# SnifferRS232.net
KiCad netlist of a schematic drawn in Altium Designer
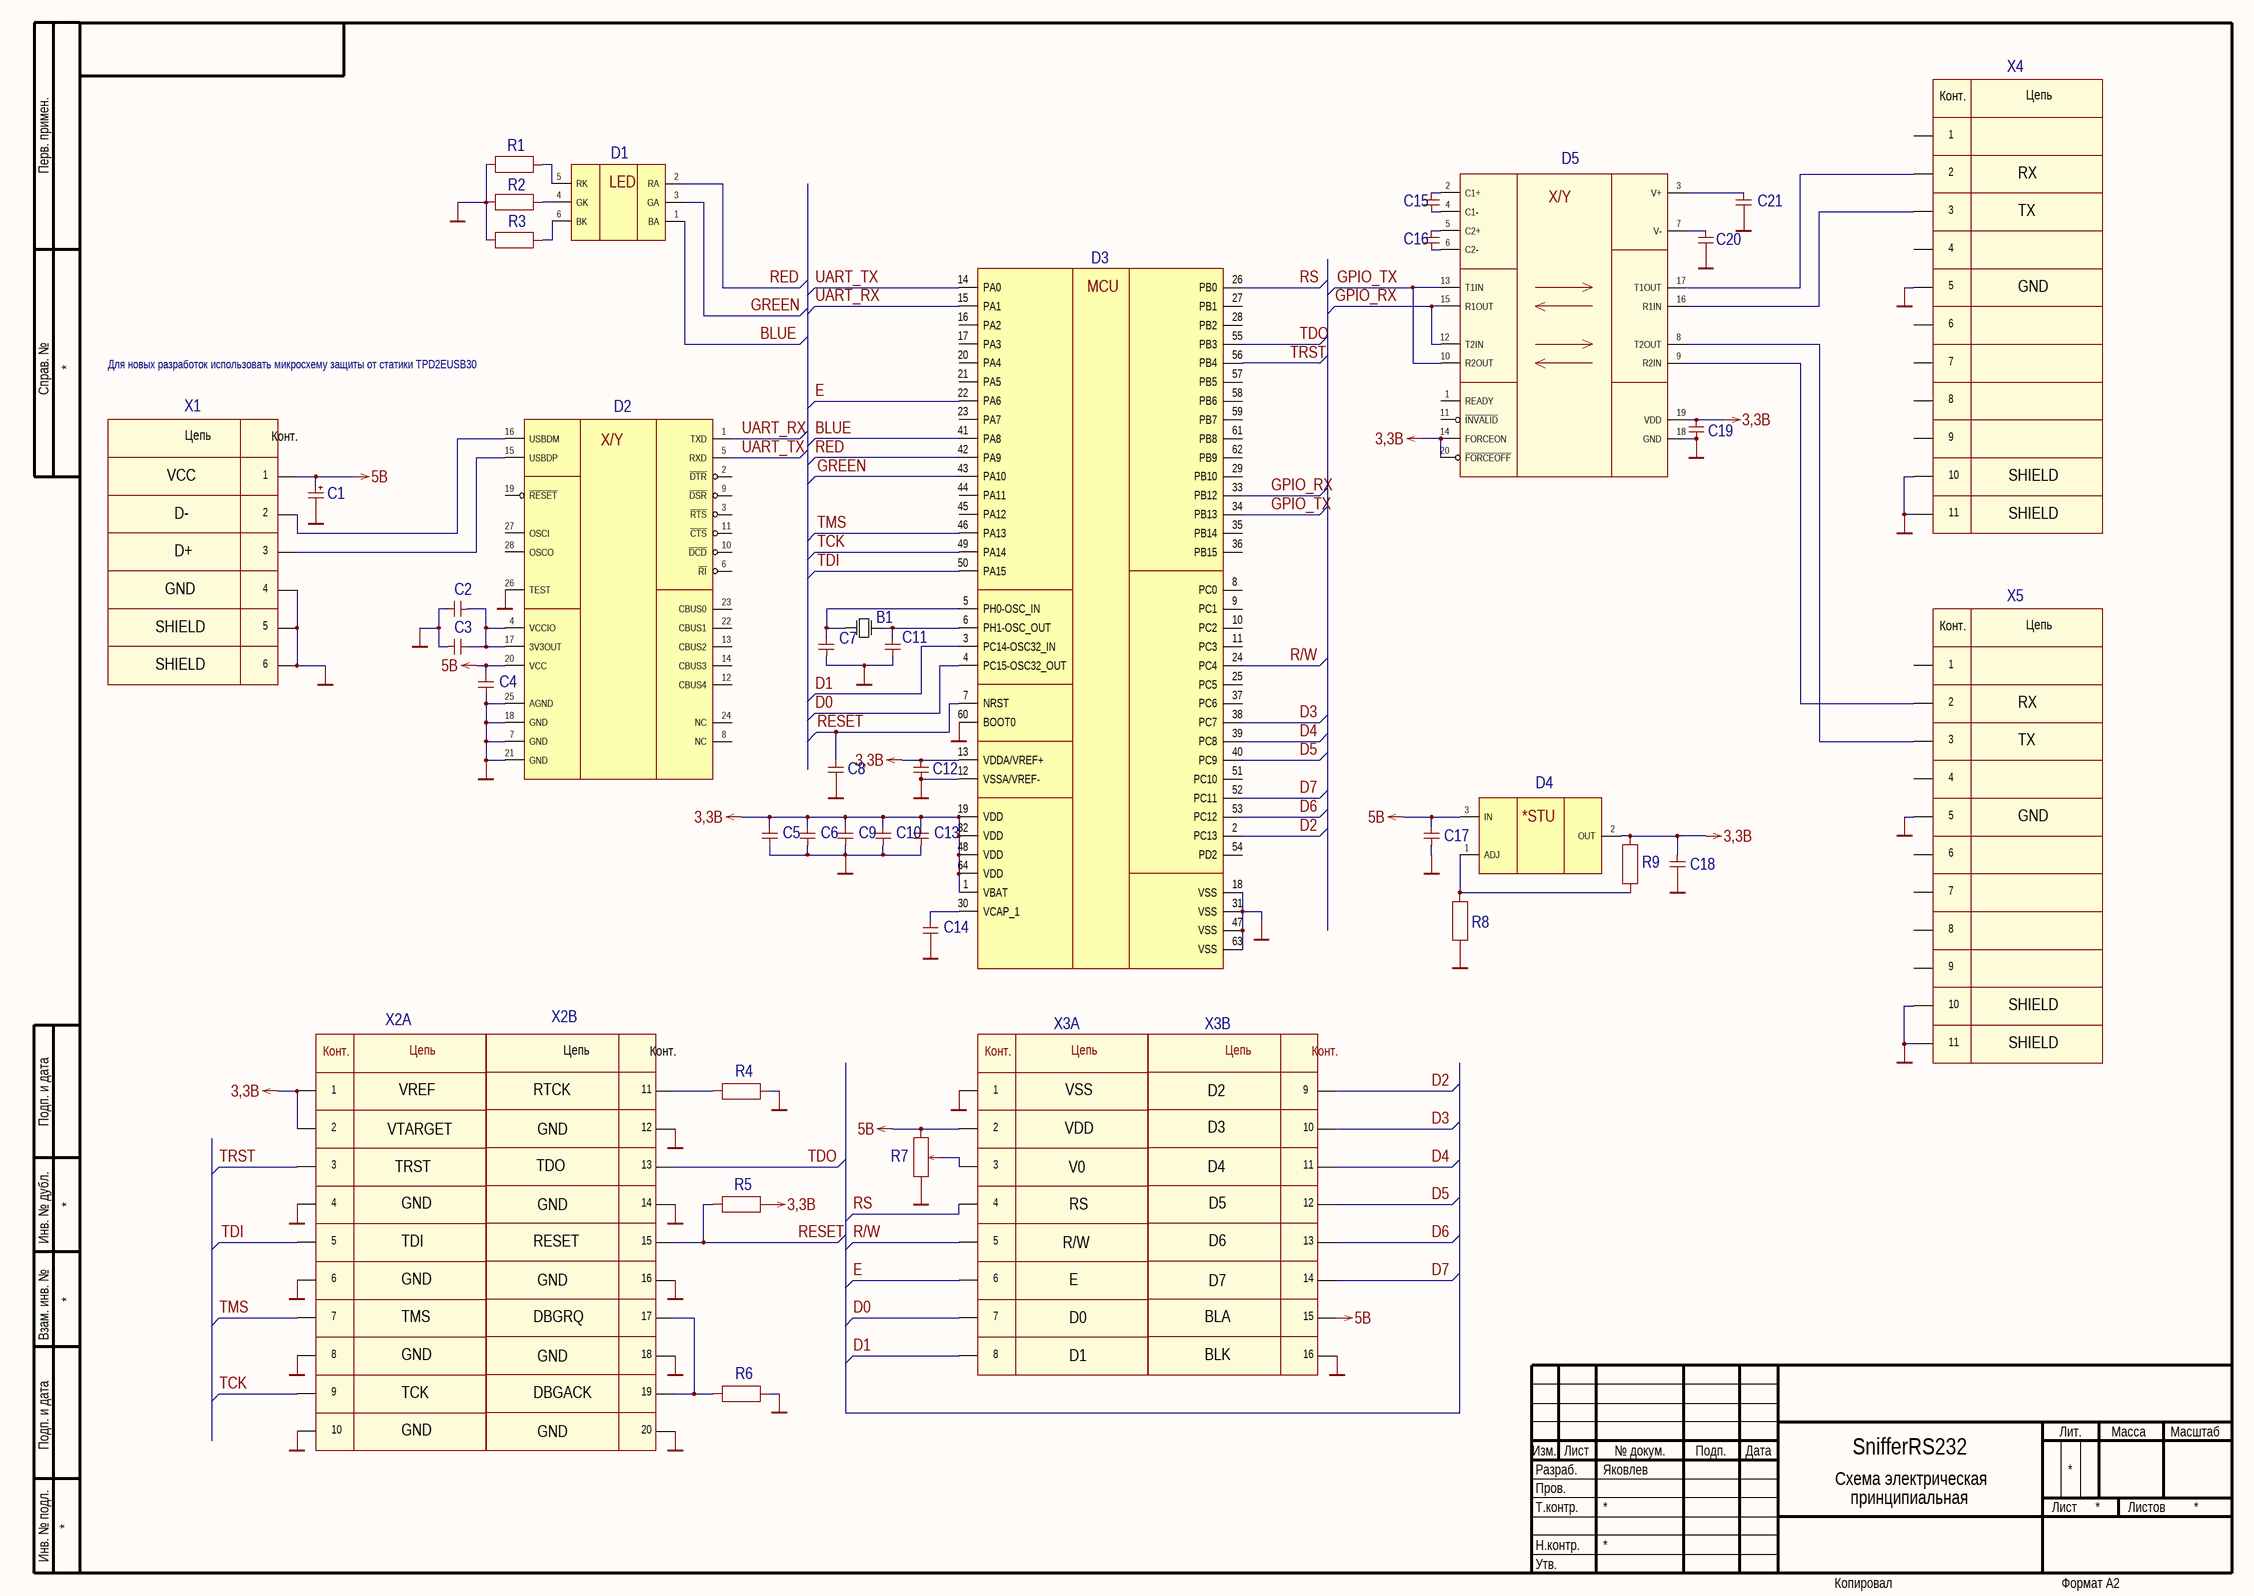
[diagram p0: SnifferRS232.SchDoc]

(export (version "E")
  (design (tool "Eeschema 10.0.6"))
  (components
    (comp (ref "B1")
      (value "ZQ1 KX-3H 25.0 MHz")
      (footprint "KX-3H")
      (description "Crystal oscillator")
      (fields (field (name "MANUFACTURER") "Geyer Electronic"))
      (libsource (lib "Devices") (part "Oscillator"))
    )
    (comp (ref "C1")
      (value "1208-16 В-100мкФ")
      (footprint "CAP_5x11")
      (description "Electrolytic capacitor")
      (libsource (lib "Passive,Diodes") (part "Cap_el"))
    )
    (comp (ref "C2")
      (value "0805-16 В-X7R-0,1мкФ±10 %")
      (footprint "SMD-0805C")
      (description "Capacitor")
      (libsource (lib "Passive,Diodes") (part "Cap"))
    )
    (comp (ref "C3")
      (value "0805-16 В-X7R-0,1мкФ±10 %")
      (footprint "SMD-0805C")
      (description "Capacitor")
      (libsource (lib "Passive,Diodes") (part "Cap"))
    )
    (comp (ref "C4")
      (value "0805-16 В-X7R-0,1мкФ±10 %")
      (footprint "SMD-0805C")
      (description "Capacitor")
      (libsource (lib "Passive,Diodes") (part "Cap"))
    )
    (comp (ref "C5")
      (value "0805-16 В-X7R-0,1мкФ±10 %")
      (footprint "SMD-0805C")
      (description "Capacitor")
      (libsource (lib "Passive,Diodes") (part "Cap"))
    )
    (comp (ref "C6")
      (value "0805-16 В-X7R-0,1мкФ±10 %")
      (footprint "SMD-0805C")
      (description "Capacitor")
      (libsource (lib "Passive,Diodes") (part "Cap"))
    )
    (comp (ref "C7")
      (value "0805-50 В-COG-22пФ±5 %")
      (footprint "SMD-0805C")
      (description "Capacitor")
      (libsource (lib "Passive,Diodes") (part "Cap"))
    )
    (comp (ref "C8")
      (value "0805-16 В-X7R-0,1мкФ±10 %")
      (footprint "SMD-0805C")
      (description "Capacitor")
      (libsource (lib "Passive,Diodes") (part "Cap"))
    )
    (comp (ref "C9")
      (value "0805-16 В-X7R-0,1мкФ±10 %")
      (footprint "SMD-0805C")
      (description "Capacitor")
      (libsource (lib "Passive,Diodes") (part "Cap"))
    )
    (comp (ref "C10")
      (value "0805-16 В-X7R-0,1мкФ±10 %")
      (footprint "SMD-0805C")
      (description "Capacitor")
      (libsource (lib "Passive,Diodes") (part "Cap"))
    )
    (comp (ref "C11")
      (value "0805-50 В-COG-22пФ±5 %")
      (footprint "SMD-0805C")
      (description "Capacitor")
      (libsource (lib "Passive,Diodes") (part "Cap"))
    )
    (comp (ref "C12")
      (value "0805-16 В-X7R-0,1мкФ±10 %")
      (footprint "SMD-0805C")
      (description "Capacitor")
      (libsource (lib "Passive,Diodes") (part "Cap"))
    )
    (comp (ref "C13")
      (value "0805-16 В-X7R-0,1мкФ±10 %")
      (footprint "SMD-0805C")
      (description "Capacitor")
      (libsource (lib "Passive,Diodes") (part "Cap"))
    )
    (comp (ref "C14")
      (value "0805-16 В-X7R-4,7мкФ±10 %")
      (footprint "SMD-0805C")
      (description "Capacitor")
      (libsource (lib "Passive,Diodes") (part "Cap"))
    )
    (comp (ref "C15")
      (value "0805-16 В-X7R-0,1мкФ±10 %")
      (footprint "SMD-0805C")
      (description "Capacitor")
      (libsource (lib "Passive,Diodes") (part "Cap"))
    )
    (comp (ref "C16")
      (value "0805-16 В-X7R-0,1мкФ±10 %")
      (footprint "SMD-0805C")
      (description "Capacitor")
      (libsource (lib "Passive,Diodes") (part "Cap"))
    )
    (comp (ref "C17")
      (value "0805-16 В-X7R-1мкФ±10 %")
      (footprint "SMD-0805C")
      (description "Capacitor")
      (libsource (lib "Passive,Diodes") (part "Cap"))
    )
    (comp (ref "C18")
      (value "0805-16 В-X7R-1мкФ±10 %")
      (footprint "SMD-0805C")
      (description "Capacitor")
      (libsource (lib "Passive,Diodes") (part "Cap"))
    )
    (comp (ref "C19")
      (value "0805-16 В-X7R-0,1мкФ±10 %")
      (footprint "SMD-0805C")
      (description "Capacitor")
      (libsource (lib "Passive,Diodes") (part "Cap"))
    )
    (comp (ref "C20")
      (value "0805-16 В-X7R-0,1мкФ±10 %")
      (footprint "SMD-0805C")
      (description "Capacitor")
      (libsource (lib "Passive,Diodes") (part "Cap"))
    )
    (comp (ref "C21")
      (value "0805-16 В-X7R-0,1мкФ±10 %")
      (footprint "SMD-0805C")
      (description "Capacitor")
      (libsource (lib "Passive,Diodes") (part "Cap"))
    )
    (comp (ref "D1")
      (value "TO-5050BC-MRPBFGF")
      (footprint "smd_50x50")
      (description "Surface mount smd LED")
      (fields (field (name "MANUFACTURER") "Oasis Technology"))
      (libsource (lib "Devices") (part "LED_RGB"))
    )
    (comp (ref "D2")
      (value "FT232RL")
      (footprint "SSOP-28_M")
      (description "USB UART Asynchronous Serial Data Transfer Chip, SSOP-28, Tape and Reel")
      (fields (field (name "MANUFACTURER") "FTDI"))
      (libsource (lib "Devices") (part "FT232R"))
    )
    (comp (ref "D3")
      (value "STM32F446RCT6")
      (footprint "LQFP64")
      (fields (field (name "MANUFACTURER") "STMicroelectronics"))
      (libsource (lib "Devices") (part "STM32F446RxT"))
    )
    (comp (ref "D4")
      (value "LM317DCYR")
      (footprint "Devices:SOT223_M")
      (description "3-Terminal Adjustable Regulator")
      (fields (field (name "MANUFACTURER") "Texas Instruments"))
      (libsource (lib "Devices") (part "LM317"))
    )
    (comp (ref "D5")
      (value "MAX3225ECAP+")
      (footprint "TSSOP-20")
      (description "±15kV ESD-Protected, 1µA, 1Mbps, 3.0V to 5.5V,  RS-232 Transceivers with AutoShutdown Plus")
      (fields (field (name "MANUFACTURER") "Maxim Integrated"))
      (libsource (lib "Devices") (part "MAX3225"))
    )
    (comp (ref "R1")
      (value "0805±5 %-680 Ом")
      (footprint "SMD-0805-RES")
      (description "Resistor")
      (libsource (lib "") (part "Res_1"))
    )
    (comp (ref "R2")
      (value "0805±5 %-680 Ом")
      (footprint "SMD-0805-RES")
      (description "Resistor")
      (libsource (lib "") (part "Res_1"))
    )
    (comp (ref "R3")
      (value "0805±5 %-0 Ом")
      (footprint "SMD-0805-RES")
      (description "Resistor")
      (libsource (lib "") (part "Res_1"))
    )
    (comp (ref "R4")
      (value "0805±5 %-10 кОм")
      (footprint "SMD-0805-RES")
      (description "Resistor")
      (libsource (lib "Passive,Diodes") (part "Res"))
    )
    (comp (ref "R5")
      (value "0805±5 %-10 кОм")
      (footprint "SMD-0805-RES")
      (description "Resistor")
      (libsource (lib "") (part "Res_1"))
    )
    (comp (ref "R6")
      (value "0805±5 %-10 кОм")
      (footprint "SMD-0805-RES")
      (description "Resistor")
      (libsource (lib "Passive,Diodes") (part "Res"))
    )
    (comp (ref "R7")
      (value "CA9PV10-10KA2020")
      (footprint "CA9V")
      (description "Potentiometer")
      (fields (field (name "MANUFACTURER") "ACP Technologies"))
      (libsource (lib "Passive,Diodes") (part "Potentiometer"))
    )
    (comp (ref "R8")
      (value "0805±1 %-2 кОм")
      (footprint "SMD-0805-RES")
      (description "Resistor")
      (libsource (lib "") (part "Res_1"))
    )
    (comp (ref "R9")
      (value "0805±1 %-1,3 кОм")
      (footprint "SMD-0805-RES")
      (description "Resistor")
      (libsource (lib "Passive,Diodes") (part "Res"))
    )
    (comp (ref "X1")
      (value "DS1099-BN0")
      (footprint "FCI USB 61729-0010BLF")
      (description "USB-B connector")
      (fields (field (name "MANUFACTURER") "Connfly Electronic"))
      (libsource (lib "Connectors") (part "USB-B"))
    )
    (comp (ref "X2")
      (value "DS1021-2*10SF11-B")
      (footprint "PLD2x10")
      (description "PLD-20 connector")
      (fields (field (name "MANUFACTURER") "Connfly Electronic"))
      (libsource (lib "") (part "PLD2x10_1"))
    )
    (comp (ref "X3")
      (value "DS1021-1*16SF112")
      (footprint "PLS-16_12")
      (description "PLD-16 connector")
      (fields (field (name "MANUFACTURER") "Connfly  Electronic"))
      (libsource (lib "") (part "PLD2x8_1"))
    )
    (comp (ref "X4")
      (value "DS1037-09FNAKT74-0CC")
      (footprint "DB-9F")
      (description "DB-9 female connector")
      (fields (field (name "MANUFACTURER") "Connfly Electronic"))
      (libsource (lib "Connectors") (part "DB-9"))
    )
    (comp (ref "X5")
      (value "DS1037-09MNAKT74-0CC")
      (footprint "DB-9M")
      (description "DB-9 male connector")
      (fields (field (name "MANUFACTURER") "Connfly Electronic"))
      (libsource (lib "Connectors") (part "DB-9"))
    )
  )
  (nets
    (net (code "1") (name "/BLUE") (class "Default")
      (node (ref "D1") (pin "1") (pinfunction "BA_1") (pintype "passive"))
      (node (ref "D3") (pin "41") (pinfunction "PA8_41") (pintype "passive"))
    )
    (net (code "2") (name "/D0") (class "Default")
      (node (ref "D3") (pin "4") (pinfunction "PC15-OSC32_OUT_4") (pintype "passive"))
      (node (ref "X3") (pin "7") (pinfunction "7_7") (pintype "passive"))
    )
    (net (code "3") (name "/D1") (class "Default")
      (node (ref "D3") (pin "3") (pinfunction "PC14-OSC32_IN_3") (pintype "passive"))
      (node (ref "X3") (pin "8") (pinfunction "8_8") (pintype "passive"))
    )
    (net (code "4") (name "/D2") (class "Default")
      (node (ref "D3") (pin "2") (pinfunction "PC13_2") (pintype "passive"))
      (node (ref "X3") (pin "9") (pinfunction "9_9") (pintype "passive"))
    )
    (net (code "5") (name "/D3") (class "Default")
      (node (ref "D3") (pin "38") (pinfunction "PC7_38") (pintype "passive"))
      (node (ref "X3") (pin "10") (pinfunction "10_10") (pintype "passive"))
    )
    (net (code "6") (name "/D4") (class "Default")
      (node (ref "D3") (pin "39") (pinfunction "PC8_39") (pintype "passive"))
      (node (ref "X3") (pin "11") (pinfunction "11_11") (pintype "passive"))
    )
    (net (code "7") (name "/D5") (class "Default")
      (node (ref "D3") (pin "40") (pinfunction "PC9_40") (pintype "passive"))
      (node (ref "X3") (pin "12") (pinfunction "12_12") (pintype "passive"))
    )
    (net (code "8") (name "/D6") (class "Default")
      (node (ref "D3") (pin "53") (pinfunction "PC12_53") (pintype "passive"))
      (node (ref "X3") (pin "13") (pinfunction "13_13") (pintype "passive"))
    )
    (net (code "9") (name "/D7") (class "Default")
      (node (ref "D3") (pin "52") (pinfunction "PC11_52") (pintype "passive"))
      (node (ref "X3") (pin "14") (pinfunction "14_14") (pintype "passive"))
    )
    (net (code "10") (name "/E") (class "Default")
      (node (ref "D3") (pin "22") (pinfunction "PA6_22") (pintype "passive"))
      (node (ref "X3") (pin "6") (pinfunction "6_6") (pintype "passive"))
    )
    (net (code "11") (name "/GPIO_RX") (class "Default")
      (node (ref "D3") (pin "33") (pinfunction "PB12_33") (pintype "passive"))
      (node (ref "D5") (pin "12") (pinfunction "T2IN_12") (pintype "passive"))
      (node (ref "D5") (pin "15") (pinfunction "R1OUT_15") (pintype "passive"))
    )
    (net (code "12") (name "/GPIO_TX") (class "Default")
      (node (ref "D3") (pin "34") (pinfunction "PB13_34") (pintype "passive"))
      (node (ref "D5") (pin "10") (pinfunction "R2OUT_10") (pintype "passive"))
      (node (ref "D5") (pin "13") (pinfunction "T1IN_13") (pintype "passive"))
    )
    (net (code "13") (name "/GREEN") (class "Default")
      (node (ref "D1") (pin "3") (pinfunction "GA_3") (pintype "passive"))
      (node (ref "D3") (pin "43") (pinfunction "PA10_43") (pintype "passive"))
    )
    (net (code "14") (name "/RED") (class "Default")
      (node (ref "D1") (pin "2") (pinfunction "RA_2") (pintype "passive"))
      (node (ref "D3") (pin "42") (pinfunction "PA9_42") (pintype "passive"))
    )
    (net (code "15") (name "/RESET") (class "Default")
      (node (ref "C8") (pin "1") (pinfunction "1_1") (pintype "passive"))
      (node (ref "D3") (pin "7") (pinfunction "NRST_7") (pintype "passive"))
      (node (ref "R5") (pin "2") (pinfunction "2_2") (pintype "passive"))
      (node (ref "X2") (pin "15") (pinfunction "15_15") (pintype "passive"))
    )
    (net (code "16") (name "/RS") (class "Default")
      (node (ref "D3") (pin "26") (pinfunction "PB0_26") (pintype "passive"))
      (node (ref "X3") (pin "4") (pinfunction "4_4") (pintype "passive"))
    )
    (net (code "17") (name "/R{slash}W") (class "Default")
      (node (ref "D3") (pin "24") (pinfunction "PC4_24") (pintype "passive"))
      (node (ref "X3") (pin "5") (pinfunction "5_5") (pintype "passive"))
    )
    (net (code "18") (name "/TCK") (class "Default")
      (node (ref "D3") (pin "49") (pinfunction "PA14_49") (pintype "passive"))
      (node (ref "X2") (pin "9") (pinfunction "9_9") (pintype "passive"))
    )
    (net (code "19") (name "/TDI") (class "Default")
      (node (ref "D3") (pin "50") (pinfunction "PA15_50") (pintype "passive"))
      (node (ref "X2") (pin "5") (pinfunction "5_5") (pintype "passive"))
    )
    (net (code "20") (name "/TDO") (class "Default")
      (node (ref "D3") (pin "55") (pinfunction "PB3_55") (pintype "passive"))
      (node (ref "X2") (pin "13") (pinfunction "13_13") (pintype "passive"))
    )
    (net (code "21") (name "/TMS") (class "Default")
      (node (ref "D3") (pin "46") (pinfunction "PA13_46") (pintype "passive"))
      (node (ref "X2") (pin "7") (pinfunction "7_7") (pintype "passive"))
    )
    (net (code "22") (name "/TRST") (class "Default")
      (node (ref "D3") (pin "56") (pinfunction "PB4_56") (pintype "passive"))
      (node (ref "X2") (pin "3") (pinfunction "3_3") (pintype "passive"))
    )
    (net (code "23") (name "/UART_RX") (class "Default")
      (node (ref "D2") (pin "1") (pinfunction "TXD_1") (pintype "passive"))
      (node (ref "D3") (pin "15") (pinfunction "PA1_15") (pintype "passive"))
    )
    (net (code "24") (name "/UART_TX") (class "Default")
      (node (ref "D2") (pin "5") (pinfunction "RXD_5") (pintype "passive"))
      (node (ref "D3") (pin "14") (pinfunction "PA0_14") (pintype "passive"))
    )
    (net (code "25") (name "3,3В") (class "Default")
      (node (ref "C10") (pin "1") (pinfunction "1_1") (pintype "passive"))
      (node (ref "C12") (pin "1") (pinfunction "1_1") (pintype "passive"))
      (node (ref "C13") (pin "1") (pinfunction "1_1") (pintype "passive"))
      (node (ref "C18") (pin "2") (pinfunction "2_2") (pintype "passive"))
      (node (ref "C19") (pin "1") (pinfunction "1_1") (pintype "passive"))
      (node (ref "C5") (pin "1") (pinfunction "1_1") (pintype "passive"))
      (node (ref "C6") (pin "1") (pinfunction "1_1") (pintype "passive"))
      (node (ref "C9") (pin "1") (pinfunction "1_1") (pintype "passive"))
      (node (ref "D3") (pin "1") (pinfunction "VBAT_1") (pintype "power_in"))
      (node (ref "D3") (pin "13") (pinfunction "VDDA/VREF+_13") (pintype "power_in"))
      (node (ref "D3") (pin "19") (pinfunction "VDD_19") (pintype "power_in"))
      (node (ref "D3") (pin "32") (pinfunction "VDD_32") (pintype "power_in"))
      (node (ref "D3") (pin "48") (pinfunction "VDD_48") (pintype "power_in"))
      (node (ref "D3") (pin "64") (pinfunction "VDD_64") (pintype "power_in"))
      (node (ref "D4") (pin "2") (pinfunction "OUT_2") (pintype "power_in"))
      (node (ref "D5") (pin "14") (pinfunction "FORCEON_14") (pintype "passive"))
      (node (ref "D5") (pin "19") (pinfunction "VDD_19") (pintype "power_in"))
      (node (ref "D5") (pin "20") (pinfunction "~{FORCEOFF}_20") (pintype "passive"))
      (node (ref "R5") (pin "1") (pinfunction "1_1") (pintype "passive"))
      (node (ref "R9") (pin "2") (pinfunction "2_2") (pintype "passive"))
      (node (ref "X2") (pin "1") (pinfunction "1_1") (pintype "passive"))
      (node (ref "X2") (pin "2") (pinfunction "2_2") (pintype "passive"))
    )
    (net (code "26") (name "5В") (class "Default")
      (node (ref "C1") (pin "1") (pinfunction "1_1") (pintype "passive"))
      (node (ref "C17") (pin "2") (pinfunction "2_2") (pintype "passive"))
      (node (ref "C4") (pin "1") (pinfunction "1_1") (pintype "passive"))
      (node (ref "D2") (pin "20") (pinfunction "VCC_20") (pintype "power_in"))
      (node (ref "D4") (pin "3") (pinfunction "IN_3") (pintype "power_in"))
      (node (ref "R7") (pin "3") (pinfunction "3_3") (pintype "passive"))
      (node (ref "X1") (pin "1") (pinfunction "1_1") (pintype "passive"))
      (node (ref "X3") (pin "15") (pinfunction "15_15") (pintype "passive"))
      (node (ref "X3") (pin "2") (pinfunction "2_2") (pintype "passive"))
    )
    (net (code "27") (name "GND") (class "Default")
      (node (ref "C1") (pin "2") (pinfunction "2_2") (pintype "passive"))
      (node (ref "C10") (pin "2") (pinfunction "2_2") (pintype "passive"))
      (node (ref "C11") (pin "2") (pinfunction "2_2") (pintype "passive"))
      (node (ref "C12") (pin "2") (pinfunction "2_2") (pintype "passive"))
      (node (ref "C13") (pin "2") (pinfunction "2_2") (pintype "passive"))
      (node (ref "C14") (pin "2") (pinfunction "2_2") (pintype "passive"))
      (node (ref "C17") (pin "1") (pinfunction "1_1") (pintype "passive"))
      (node (ref "C18") (pin "1") (pinfunction "1_1") (pintype "passive"))
      (node (ref "C19") (pin "2") (pinfunction "2_2") (pintype "passive"))
      (node (ref "C2") (pin "1") (pinfunction "1_1") (pintype "passive"))
      (node (ref "C20") (pin "2") (pinfunction "2_2") (pintype "passive"))
      (node (ref "C21") (pin "2") (pinfunction "2_2") (pintype "passive"))
      (node (ref "C3") (pin "1") (pinfunction "1_1") (pintype "passive"))
      (node (ref "C4") (pin "2") (pinfunction "2_2") (pintype "passive"))
      (node (ref "C5") (pin "2") (pinfunction "2_2") (pintype "passive"))
      (node (ref "C6") (pin "2") (pinfunction "2_2") (pintype "passive"))
      (node (ref "C7") (pin "2") (pinfunction "2_2") (pintype "passive"))
      (node (ref "C8") (pin "2") (pinfunction "2_2") (pintype "passive"))
      (node (ref "C9") (pin "2") (pinfunction "2_2") (pintype "passive"))
      (node (ref "D2") (pin "18") (pinfunction "GND_18") (pintype "power_in"))
      (node (ref "D2") (pin "21") (pinfunction "GND_21") (pintype "power_in"))
      (node (ref "D2") (pin "25") (pinfunction "AGND_25") (pintype "power_in"))
      (node (ref "D2") (pin "26") (pinfunction "TEST_26") (pintype "passive"))
      (node (ref "D2") (pin "7") (pinfunction "GND_7") (pintype "power_in"))
      (node (ref "D3") (pin "12") (pinfunction "VSSA/VREF-_12") (pintype "power_in"))
      (node (ref "D3") (pin "18") (pinfunction "VSS_18") (pintype "power_in"))
      (node (ref "D3") (pin "31") (pinfunction "VSS_31") (pintype "power_in"))
      (node (ref "D3") (pin "47") (pinfunction "VSS_47") (pintype "power_in"))
      (node (ref "D3") (pin "60") (pinfunction "BOOT0_60") (pintype "passive"))
      (node (ref "D3") (pin "63") (pinfunction "VSS_63") (pintype "power_in"))
      (node (ref "D5") (pin "18") (pinfunction "GND_18") (pintype "power_in"))
      (node (ref "R1") (pin "2") (pinfunction "2_2") (pintype "passive"))
      (node (ref "R2") (pin "2") (pinfunction "2_2") (pintype "passive"))
      (node (ref "R3") (pin "2") (pinfunction "2_2") (pintype "passive"))
      (node (ref "R4") (pin "2") (pinfunction "2_2") (pintype "passive"))
      (node (ref "R6") (pin "2") (pinfunction "2_2") (pintype "passive"))
      (node (ref "R7") (pin "1") (pinfunction "1_1") (pintype "passive"))
      (node (ref "R8") (pin "2") (pinfunction "2_2") (pintype "passive"))
      (node (ref "X1") (pin "4") (pinfunction "4_4") (pintype "passive"))
      (node (ref "X1") (pin "5") (pinfunction "5_5") (pintype "passive"))
      (node (ref "X1") (pin "6") (pinfunction "6_6") (pintype "passive"))
      (node (ref "X2") (pin "10") (pinfunction "10_10") (pintype "passive"))
      (node (ref "X2") (pin "12") (pinfunction "12_12") (pintype "passive"))
      (node (ref "X2") (pin "14") (pinfunction "14_14") (pintype "passive"))
      (node (ref "X2") (pin "16") (pinfunction "16_16") (pintype "passive"))
      (node (ref "X2") (pin "18") (pinfunction "18_18") (pintype "passive"))
      (node (ref "X2") (pin "20") (pinfunction "20_20") (pintype "passive"))
      (node (ref "X2") (pin "4") (pinfunction "4_4") (pintype "passive"))
      (node (ref "X2") (pin "6") (pinfunction "6_6") (pintype "passive"))
      (node (ref "X2") (pin "8") (pinfunction "8_8") (pintype "passive"))
      (node (ref "X3") (pin "1") (pinfunction "1_1") (pintype "passive"))
      (node (ref "X3") (pin "16") (pinfunction "16_16") (pintype "passive"))
      (node (ref "X4") (pin "10") (pinfunction "10_10") (pintype "passive"))
      (node (ref "X4") (pin "11") (pinfunction "11_11") (pintype "passive"))
      (node (ref "X4") (pin "5") (pinfunction "5_5") (pintype "passive"))
      (node (ref "X5") (pin "10") (pinfunction "10_10") (pintype "passive"))
      (node (ref "X5") (pin "11") (pinfunction "11_11") (pintype "passive"))
      (node (ref "X5") (pin "5") (pinfunction "5_5") (pintype "passive"))
    )
    (net (code "28") (name "Net-(B1-OSCIN)") (class "Default")
      (node (ref "B1") (pin "1") (pinfunction "OSCIN_1") (pintype "passive"))
      (node (ref "C11") (pin "1") (pinfunction "1_1") (pintype "passive"))
      (node (ref "D3") (pin "6") (pinfunction "PH1-OSC_OUT_6") (pintype "passive"))
    )
    (net (code "29") (name "Net-(B1-OSCOUT)") (class "Default")
      (node (ref "B1") (pin "2") (pinfunction "OSCOUT_2") (pintype "passive"))
      (node (ref "C7") (pin "1") (pinfunction "1_1") (pintype "passive"))
      (node (ref "D3") (pin "5") (pinfunction "PH0-OSC_IN_5") (pintype "passive"))
    )
    (net (code "30") (name "Net-(D1-BK)") (class "Default")
      (node (ref "D1") (pin "6") (pinfunction "BK_6") (pintype "passive"))
      (node (ref "R3") (pin "1") (pinfunction "1_1") (pintype "passive"))
    )
    (net (code "31") (name "Net-(D1-GK)") (class "Default")
      (node (ref "D1") (pin "4") (pinfunction "GK_4") (pintype "passive"))
      (node (ref "R2") (pin "1") (pinfunction "1_1") (pintype "passive"))
    )
    (net (code "32") (name "Net-(D1-RK)") (class "Default")
      (node (ref "D1") (pin "5") (pinfunction "RK_5") (pintype "passive"))
      (node (ref "R1") (pin "1") (pinfunction "1_1") (pintype "passive"))
    )
    (net (code "33") (name "Net-(D2-3V3OUT)") (class "Default")
      (node (ref "C2") (pin "2") (pinfunction "2_2") (pintype "passive"))
      (node (ref "C3") (pin "2") (pinfunction "2_2") (pintype "passive"))
      (node (ref "D2") (pin "17") (pinfunction "3V3OUT_17") (pintype "power_in"))
      (node (ref "D2") (pin "4") (pinfunction "VCCIO_4") (pintype "power_in"))
    )
    (net (code "34") (name "Net-(D2-USBDM)") (class "Default")
      (node (ref "D2") (pin "16") (pinfunction "USBDM_16") (pintype "passive"))
      (node (ref "X1") (pin "2") (pinfunction "2_2") (pintype "passive"))
    )
    (net (code "35") (name "Net-(D2-USBDP)") (class "Default")
      (node (ref "D2") (pin "15") (pinfunction "USBDP_15") (pintype "passive"))
      (node (ref "X1") (pin "3") (pinfunction "3_3") (pintype "passive"))
    )
    (net (code "36") (name "Net-(D3-VCAP_1)") (class "Default")
      (node (ref "C14") (pin "1") (pinfunction "1_1") (pintype "passive"))
      (node (ref "D3") (pin "30") (pinfunction "VCAP_1_30") (pintype "passive"))
    )
    (net (code "37") (name "Net-(D4-ADJ)") (class "Default")
      (node (ref "D4") (pin "1") (pinfunction "ADJ_1") (pintype "passive"))
      (node (ref "R8") (pin "1") (pinfunction "1_1") (pintype "passive"))
      (node (ref "R9") (pin "1") (pinfunction "1_1") (pintype "passive"))
    )
    (net (code "38") (name "Net-(D5-C1+)") (class "Default")
      (node (ref "C15") (pin "1") (pinfunction "1_1") (pintype "passive"))
      (node (ref "D5") (pin "2") (pinfunction "C1+_2") (pintype "passive"))
    )
    (net (code "39") (name "Net-(D5-C1-)") (class "Default")
      (node (ref "C15") (pin "2") (pinfunction "2_2") (pintype "passive"))
      (node (ref "D5") (pin "4") (pinfunction "C1-_4") (pintype "passive"))
    )
    (net (code "40") (name "Net-(D5-C2+)") (class "Default")
      (node (ref "C16") (pin "1") (pinfunction "1_1") (pintype "passive"))
      (node (ref "D5") (pin "5") (pinfunction "C2+_5") (pintype "passive"))
    )
    (net (code "41") (name "Net-(D5-C2-)") (class "Default")
      (node (ref "C16") (pin "2") (pinfunction "2_2") (pintype "passive"))
      (node (ref "D5") (pin "6") (pinfunction "C2-_6") (pintype "passive"))
    )
    (net (code "42") (name "Net-(D5-R1IN)") (class "Default")
      (node (ref "D5") (pin "16") (pinfunction "R1IN_16") (pintype "passive"))
      (node (ref "X4") (pin "3") (pinfunction "3_3") (pintype "passive"))
    )
    (net (code "43") (name "Net-(D5-R2IN)") (class "Default")
      (node (ref "D5") (pin "9") (pinfunction "R2IN_9") (pintype "passive"))
      (node (ref "X5") (pin "2") (pinfunction "2_2") (pintype "passive"))
    )
    (net (code "44") (name "Net-(D5-T1OUT)") (class "Default")
      (node (ref "D5") (pin "17") (pinfunction "T1OUT_17") (pintype "passive"))
      (node (ref "X4") (pin "2") (pinfunction "2_2") (pintype "passive"))
    )
    (net (code "45") (name "Net-(D5-T2OUT)") (class "Default")
      (node (ref "D5") (pin "8") (pinfunction "T2OUT_8") (pintype "passive"))
      (node (ref "X5") (pin "3") (pinfunction "3_3") (pintype "passive"))
    )
    (net (code "46") (name "Net-(D5-V+)") (class "Default")
      (node (ref "C21") (pin "1") (pinfunction "1_1") (pintype "passive"))
      (node (ref "D5") (pin "3") (pinfunction "V+_3") (pintype "power_in"))
    )
    (net (code "47") (name "Net-(D5-V-)") (class "Default")
      (node (ref "C20") (pin "1") (pinfunction "1_1") (pintype "passive"))
      (node (ref "D5") (pin "7") (pinfunction "V-_7") (pintype "power_in"))
    )
    (net (code "48") (name "Net-(R4-Pad1)") (class "Default")
      (node (ref "R4") (pin "1") (pinfunction "1_1") (pintype "passive"))
      (node (ref "X2") (pin "11") (pinfunction "11_11") (pintype "passive"))
    )
    (net (code "49") (name "Net-(R6-Pad1)") (class "Default")
      (node (ref "R6") (pin "1") (pinfunction "1_1") (pintype "passive"))
      (node (ref "X2") (pin "17") (pinfunction "17_17") (pintype "passive"))
      (node (ref "X2") (pin "19") (pinfunction "19_19") (pintype "passive"))
    )
    (net (code "50") (name "Net-(R7-Pad2)") (class "Default")
      (node (ref "R7") (pin "2") (pinfunction "2_2") (pintype "passive"))
      (node (ref "X3") (pin "3") (pinfunction "3_3") (pintype "passive"))
    )
    (net (code "51") (name "unconnected-(D2-CBUS0-Pad23)") (class "Default")
      (node (ref "D2") (pin "23") (pinfunction "CBUS0_23") (pintype "passive"))
    )
    (net (code "52") (name "unconnected-(D2-CBUS1-Pad22)") (class "Default")
      (node (ref "D2") (pin "22") (pinfunction "CBUS1_22") (pintype "passive"))
    )
    (net (code "53") (name "unconnected-(D2-CBUS2-Pad13)") (class "Default")
      (node (ref "D2") (pin "13") (pinfunction "CBUS2_13") (pintype "passive"))
    )
    (net (code "54") (name "unconnected-(D2-CBUS3-Pad14)") (class "Default")
      (node (ref "D2") (pin "14") (pinfunction "CBUS3_14") (pintype "passive"))
    )
    (net (code "55") (name "unconnected-(D2-CBUS4-Pad12)") (class "Default")
      (node (ref "D2") (pin "12") (pinfunction "CBUS4_12") (pintype "passive"))
    )
    (net (code "56") (name "unconnected-(D2-NC-Pad8)") (class "Default")
      (node (ref "D2") (pin "8") (pinfunction "NC_8") (pintype "passive"))
    )
    (net (code "57") (name "unconnected-(D2-NC-Pad24)") (class "Default")
      (node (ref "D2") (pin "24") (pinfunction "NC_24") (pintype "passive"))
    )
    (net (code "58") (name "unconnected-(D2-OSCI-Pad27)") (class "Default")
      (node (ref "D2") (pin "27") (pinfunction "OSCI_27") (pintype "passive"))
    )
    (net (code "59") (name "unconnected-(D2-OSCO-Pad28)") (class "Default")
      (node (ref "D2") (pin "28") (pinfunction "OSCO_28") (pintype "passive"))
    )
    (net (code "60") (name "unconnected-(D2-~{CTS}-Pad11)") (class "Default")
      (node (ref "D2") (pin "11") (pinfunction "~{CTS}_11") (pintype "passive"))
    )
    (net (code "61") (name "unconnected-(D2-~{DCD}-Pad10)") (class "Default")
      (node (ref "D2") (pin "10") (pinfunction "~{DCD}_10") (pintype "passive"))
    )
    (net (code "62") (name "unconnected-(D2-~{DSR}-Pad9)") (class "Default")
      (node (ref "D2") (pin "9") (pinfunction "~{DSR}_9") (pintype "passive"))
    )
    (net (code "63") (name "unconnected-(D2-~{DTR}-Pad2)") (class "Default")
      (node (ref "D2") (pin "2") (pinfunction "~{DTR}_2") (pintype "passive"))
    )
    (net (code "64") (name "unconnected-(D2-~{RESET}-Pad19)") (class "Default")
      (node (ref "D2") (pin "19") (pinfunction "~{RESET}_19") (pintype "passive"))
    )
    (net (code "65") (name "unconnected-(D2-~{RI}-Pad6)") (class "Default")
      (node (ref "D2") (pin "6") (pinfunction "~{RI}_6") (pintype "passive"))
    )
    (net (code "66") (name "unconnected-(D2-~{RTS}-Pad3)") (class "Default")
      (node (ref "D2") (pin "3") (pinfunction "~{RTS}_3") (pintype "passive"))
    )
    (net (code "67") (name "unconnected-(D3-PA2-Pad16)") (class "Default")
      (node (ref "D3") (pin "16") (pinfunction "PA2_16") (pintype "passive"))
    )
    (net (code "68") (name "unconnected-(D3-PA3-Pad17)") (class "Default")
      (node (ref "D3") (pin "17") (pinfunction "PA3_17") (pintype "passive"))
    )
    (net (code "69") (name "unconnected-(D3-PA4-Pad20)") (class "Default")
      (node (ref "D3") (pin "20") (pinfunction "PA4_20") (pintype "passive"))
    )
    (net (code "70") (name "unconnected-(D3-PA5-Pad21)") (class "Default")
      (node (ref "D3") (pin "21") (pinfunction "PA5_21") (pintype "passive"))
    )
    (net (code "71") (name "unconnected-(D3-PA7-Pad23)") (class "Default")
      (node (ref "D3") (pin "23") (pinfunction "PA7_23") (pintype "passive"))
    )
    (net (code "72") (name "unconnected-(D3-PA11-Pad44)") (class "Default")
      (node (ref "D3") (pin "44") (pinfunction "PA11_44") (pintype "passive"))
    )
    (net (code "73") (name "unconnected-(D3-PA12-Pad45)") (class "Default")
      (node (ref "D3") (pin "45") (pinfunction "PA12_45") (pintype "passive"))
    )
    (net (code "74") (name "unconnected-(D3-PB1-Pad27)") (class "Default")
      (node (ref "D3") (pin "27") (pinfunction "PB1_27") (pintype "passive"))
    )
    (net (code "75") (name "unconnected-(D3-PB2-Pad28)") (class "Default")
      (node (ref "D3") (pin "28") (pinfunction "PB2_28") (pintype "passive"))
    )
    (net (code "76") (name "unconnected-(D3-PB5-Pad57)") (class "Default")
      (node (ref "D3") (pin "57") (pinfunction "PB5_57") (pintype "passive"))
    )
    (net (code "77") (name "unconnected-(D3-PB6-Pad58)") (class "Default")
      (node (ref "D3") (pin "58") (pinfunction "PB6_58") (pintype "passive"))
    )
    (net (code "78") (name "unconnected-(D3-PB7-Pad59)") (class "Default")
      (node (ref "D3") (pin "59") (pinfunction "PB7_59") (pintype "passive"))
    )
    (net (code "79") (name "unconnected-(D3-PB8-Pad61)") (class "Default")
      (node (ref "D3") (pin "61") (pinfunction "PB8_61") (pintype "passive"))
    )
    (net (code "80") (name "unconnected-(D3-PB9-Pad62)") (class "Default")
      (node (ref "D3") (pin "62") (pinfunction "PB9_62") (pintype "passive"))
    )
    (net (code "81") (name "unconnected-(D3-PB10-Pad29)") (class "Default")
      (node (ref "D3") (pin "29") (pinfunction "PB10_29") (pintype "passive"))
    )
    (net (code "82") (name "unconnected-(D3-PB14-Pad35)") (class "Default")
      (node (ref "D3") (pin "35") (pinfunction "PB14_35") (pintype "passive"))
    )
    (net (code "83") (name "unconnected-(D3-PB15-Pad36)") (class "Default")
      (node (ref "D3") (pin "36") (pinfunction "PB15_36") (pintype "passive"))
    )
    (net (code "84") (name "unconnected-(D3-PC0-Pad8)") (class "Default")
      (node (ref "D3") (pin "8") (pinfunction "PC0_8") (pintype "passive"))
    )
    (net (code "85") (name "unconnected-(D3-PC1-Pad9)") (class "Default")
      (node (ref "D3") (pin "9") (pinfunction "PC1_9") (pintype "passive"))
    )
    (net (code "86") (name "unconnected-(D3-PC2-Pad10)") (class "Default")
      (node (ref "D3") (pin "10") (pinfunction "PC2_10") (pintype "passive"))
    )
    (net (code "87") (name "unconnected-(D3-PC3-Pad11)") (class "Default")
      (node (ref "D3") (pin "11") (pinfunction "PC3_11") (pintype "passive"))
    )
    (net (code "88") (name "unconnected-(D3-PC5-Pad25)") (class "Default")
      (node (ref "D3") (pin "25") (pinfunction "PC5_25") (pintype "passive"))
    )
    (net (code "89") (name "unconnected-(D3-PC6-Pad37)") (class "Default")
      (node (ref "D3") (pin "37") (pinfunction "PC6_37") (pintype "passive"))
    )
    (net (code "90") (name "unconnected-(D3-PC10-Pad51)") (class "Default")
      (node (ref "D3") (pin "51") (pinfunction "PC10_51") (pintype "passive"))
    )
    (net (code "91") (name "unconnected-(D3-PD2-Pad54)") (class "Default")
      (node (ref "D3") (pin "54") (pinfunction "PD2_54") (pintype "passive"))
    )
    (net (code "92") (name "unconnected-(D5-READY-Pad1)") (class "Default")
      (node (ref "D5") (pin "1") (pinfunction "READY_1") (pintype "passive"))
    )
    (net (code "93") (name "unconnected-(D5-~{INVALID}-Pad11)") (class "Default")
      (node (ref "D5") (pin "11") (pinfunction "~{INVALID}_11") (pintype "passive"))
    )
    (net (code "94") (name "unconnected-(X4-Pad1)") (class "Default")
      (node (ref "X4") (pin "1") (pinfunction "1_1") (pintype "passive"))
    )
    (net (code "95") (name "unconnected-(X4-Pad4)") (class "Default")
      (node (ref "X4") (pin "4") (pinfunction "4_4") (pintype "passive"))
    )
    (net (code "96") (name "unconnected-(X4-Pad6)") (class "Default")
      (node (ref "X4") (pin "6") (pinfunction "6_6") (pintype "passive"))
    )
    (net (code "97") (name "unconnected-(X4-Pad7)") (class "Default")
      (node (ref "X4") (pin "7") (pinfunction "7_7") (pintype "passive"))
    )
    (net (code "98") (name "unconnected-(X4-Pad8)") (class "Default")
      (node (ref "X4") (pin "8") (pinfunction "8_8") (pintype "passive"))
    )
    (net (code "99") (name "unconnected-(X4-Pad9)") (class "Default")
      (node (ref "X4") (pin "9") (pinfunction "9_9") (pintype "passive"))
    )
    (net (code "100") (name "unconnected-(X5-Pad1)") (class "Default")
      (node (ref "X5") (pin "1") (pinfunction "1_1") (pintype "passive"))
    )
    (net (code "101") (name "unconnected-(X5-Pad4)") (class "Default")
      (node (ref "X5") (pin "4") (pinfunction "4_4") (pintype "passive"))
    )
    (net (code "102") (name "unconnected-(X5-Pad6)") (class "Default")
      (node (ref "X5") (pin "6") (pinfunction "6_6") (pintype "passive"))
    )
    (net (code "103") (name "unconnected-(X5-Pad7)") (class "Default")
      (node (ref "X5") (pin "7") (pinfunction "7_7") (pintype "passive"))
    )
    (net (code "104") (name "unconnected-(X5-Pad8)") (class "Default")
      (node (ref "X5") (pin "8") (pinfunction "8_8") (pintype "passive"))
    )
    (net (code "105") (name "unconnected-(X5-Pad9)") (class "Default")
      (node (ref "X5") (pin "9") (pinfunction "9_9") (pintype "passive"))
    )
  )
)
